# Sheet2.net
KiCad netlist of a schematic drawn in Altium Designer
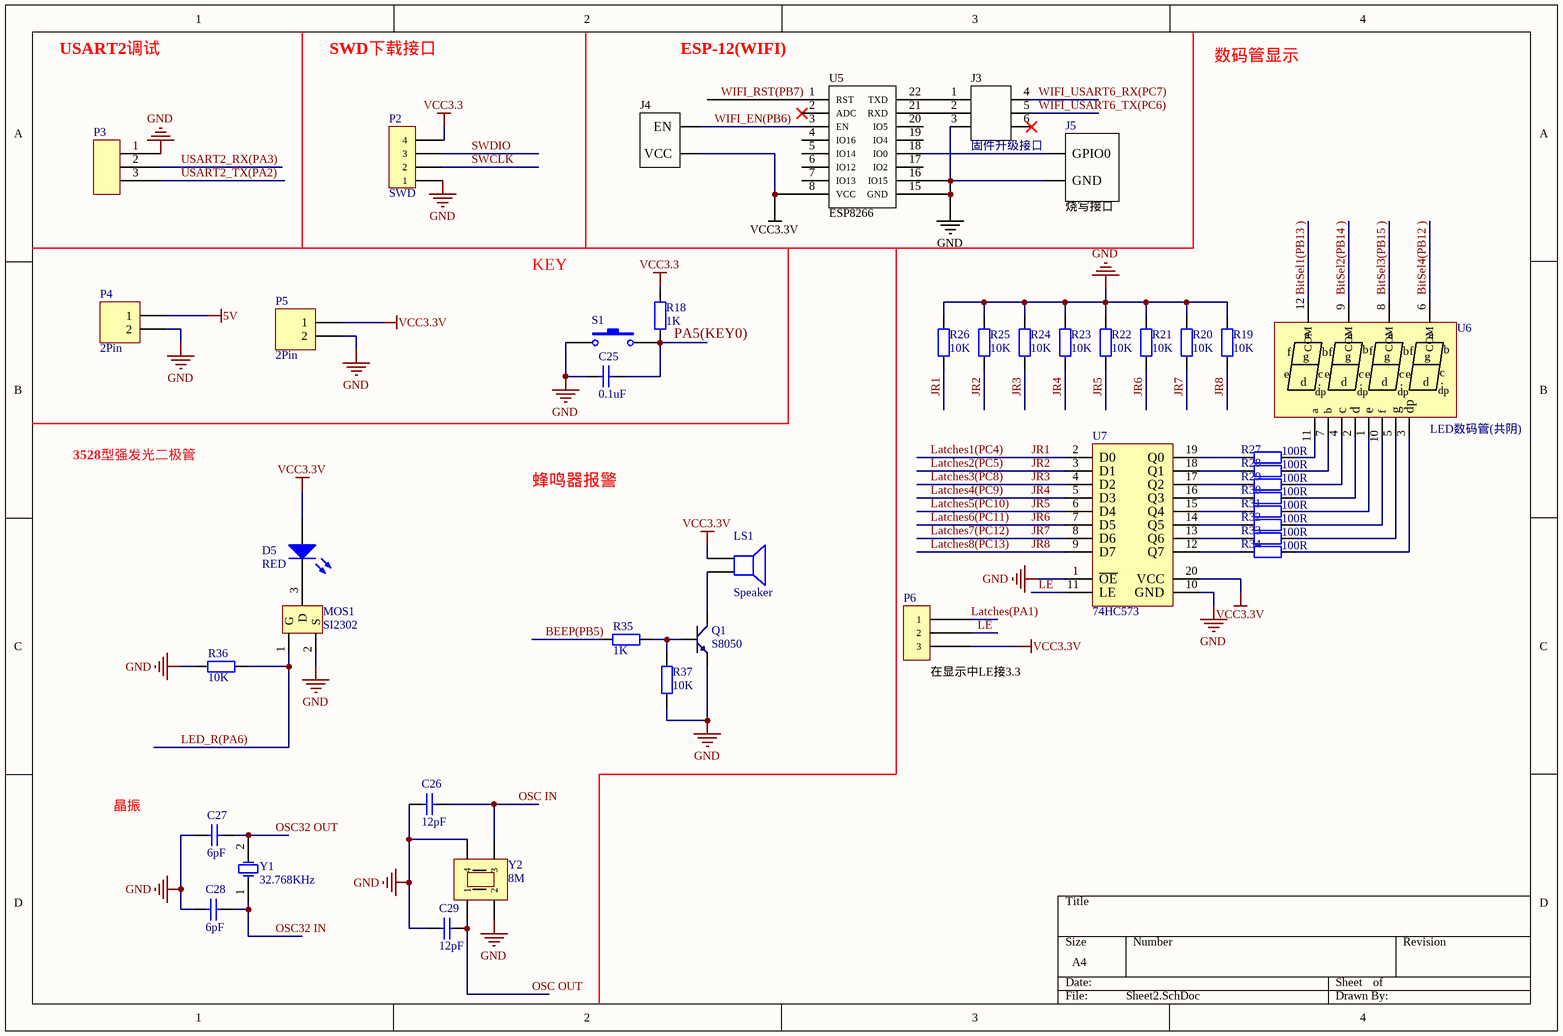
[diagram p0: Sheet2.SchDoc]

(export (version "E")
  (design (tool "Eeschema 10.0.6"))
  (components
    (comp (ref "C25")
      (value "0.1uF")
      (footprint "LC-0603_C(普通电容)")
      (description "贴片电容")
      (fields (field (name "PUBLISHER") "Altium Limited"))
      (libsource (lib "Miscellaneous Devices") (part "Cap Semi"))
    )
    (comp (ref "C26")
      (value "22pF")
      (footprint "LC-0603_C(普通电容)")
      (description "贴片电阻")
      (fields (field (name "值") "12pF") (field (name "PUBLISHER") "Altium Limited"))
      (libsource (lib "Miscellaneous Devices") (part "Cap Semi"))
    )
    (comp (ref "C27")
      (value "6pF")
      (footprint "LC-0603_C(普通电容)")
      (description "贴片电阻")
      (fields (field (name "PUBLISHER") "Altium Limited"))
      (libsource (lib "Miscellaneous Devices") (part "Cap Semi"))
    )
    (comp (ref "C28")
      (value "6pF")
      (footprint "LC-0603_C(普通电容)")
      (description "贴片电阻")
      (fields (field (name "值") "6pF") (field (name "PUBLISHER") "Altium Limited"))
      (libsource (lib "Miscellaneous Devices") (part "Cap Semi"))
    )
    (comp (ref "C29")
      (value "22pF")
      (footprint "LC-0603_C(普通电容)")
      (description "贴片电容")
      (fields (field (name "值") "12pF") (field (name "PUBLISHER") "Altium Limited"))
      (libsource (lib "Miscellaneous Devices") (part "Cap Semi"))
    )
    (comp (ref "D5")
      (value "RED")
      (footprint "发光二极管(CASE-B_3528国星光电)")
      (description "发光二极管")
      (libsource (lib "Miscellaneous Devices") (part "LED2"))
    )
    (comp (ref "J3")
      (value "固件升级接口")
      (footprint "Header2*3 2.54mm")
      (description "固件升级接口2.54mm")
      (libsource (lib "Schlib1") (part "Header2*3"))
    )
    (comp (ref "J4")
      (value "烧录接口")
      (footprint "Header1*2 2.54mm")
      (description "烧录接口2.54mm")
      (libsource (lib "Schlib1") (part "ESP烧录"))
    )
    (comp (ref "J5")
      (value "烧写接口")
      (footprint "Header1*2 2.54mm")
      (description "烧写接口2.54mm")
      (libsource (lib "Schlib1") (part "Header1*2 2.54mm"))
    )
    (comp (ref "LS1")
      (value "Speaker")
      (footprint "PcbLib1:BEEP")
      (description "Loudspeaker")
      (libsource (lib "Schlib1") (part "Speaker"))
    )
    (comp (ref "MOS1")
      (value "SI2302")
      (footprint "MOS(SOP-23美微科)")
      (description "AP2306")
      (libsource (lib "Schlib1") (part "MOS-N"))
    )
    (comp (ref "P2")
      (value "SWD")
      (footprint "Header1*4 2.54MM")
      (description "杜邦线2.54")
      (libsource (lib "PCB") (part "JMP2"))
    )
    (comp (ref "P3")
      (value "串口2调试")
      (footprint "Header1*3 2.54mm")
      (description "排针 2.54MM")
      (libsource (lib "PCB") (part "SIP"))
    )
    (comp (ref "P4")
      (value "2Pin")
      (footprint "PcbLib1:Header1*2 2.54mm")
      (description "Header, 2-Pin")
      (libsource (lib "Schlib1") (part "Header 2"))
    )
    (comp (ref "P5")
      (value "2Pin")
      (footprint "PcbLib1:Header1*2 2.54mm")
      (description "Header, 2-Pin")
      (libsource (lib "Schlib1") (part "Header 2"))
    )
    (comp (ref "P6")
      (value "3P供电选择")
      (footprint "Header1*3 2.54mm")
      (description "排针 2.54MM")
      (libsource (lib "Schlib1") (part "SIP"))
    )
    (comp (ref "Q1")
      (value "S8050")
      (footprint "SOP-23(NPN江苏长电)")
      (description "NPN")
      (libsource (lib "Schlib1") (part "S8050"))
    )
    (comp (ref "R18")
      (value "1K")
      (footprint "LC-0603_R(电阻)")
      (description "贴片电阻")
      (fields (field (name "PUBLISHER") "Altium Limited"))
      (libsource (lib "") (part "Res2_2"))
    )
    (comp (ref "R19")
      (value "10K")
      (footprint "LC-0603_R(电阻)")
      (description "贴片电阻")
      (fields (field (name "Comment") "10k") (field (name "PUBLISHER") "Altium Limited"))
      (libsource (lib "Miscellaneous Devices") (part "Res2"))
    )
    (comp (ref "R20")
      (value "10K")
      (footprint "LC-0603_R(电阻)")
      (description "贴片电阻")
      (fields (field (name "Comment") "10k") (field (name "PUBLISHER") "Altium Limited"))
      (libsource (lib "Miscellaneous Devices") (part "Res2"))
    )
    (comp (ref "R21")
      (value "10K")
      (footprint "LC-0603_R(电阻)")
      (description "贴片电阻")
      (fields (field (name "Comment") "10k") (field (name "PUBLISHER") "Altium Limited"))
      (libsource (lib "Miscellaneous Devices") (part "Res2"))
    )
    (comp (ref "R22")
      (value "10K")
      (footprint "LC-0603_R(电阻)")
      (description "贴片电阻")
      (fields (field (name "Comment") "10k") (field (name "PUBLISHER") "Altium Limited"))
      (libsource (lib "Miscellaneous Devices") (part "Res2"))
    )
    (comp (ref "R23")
      (value "10K")
      (footprint "LC-0603_R(电阻)")
      (description "贴片电阻")
      (fields (field (name "Comment") "10k") (field (name "PUBLISHER") "Altium Limited"))
      (libsource (lib "Miscellaneous Devices") (part "Res2"))
    )
    (comp (ref "R24")
      (value "10K")
      (footprint "LC-0603_R(电阻)")
      (description "贴片电阻")
      (fields (field (name "Comment") "10k") (field (name "PUBLISHER") "Altium Limited"))
      (libsource (lib "Miscellaneous Devices") (part "Res2"))
    )
    (comp (ref "R25")
      (value "10K")
      (footprint "LC-0603_R(电阻)")
      (description "贴片电阻")
      (fields (field (name "Comment") "10k") (field (name "PUBLISHER") "Altium Limited"))
      (libsource (lib "Miscellaneous Devices") (part "Res2"))
    )
    (comp (ref "R26")
      (value "10K")
      (footprint "LC-0603_R(电阻)")
      (description "贴片电阻")
      (fields (field (name "Comment") "10k") (field (name "PUBLISHER") "Altium Limited"))
      (libsource (lib "Miscellaneous Devices") (part "Res2"))
    )
    (comp (ref "R27")
      (value "100R")
      (footprint "LC-0603_R(电阻)")
      (description "贴片电阻")
      (fields (field (name "Comment") "10k") (field (name "PUBLISHER") "Altium Limited"))
      (libsource (lib "") (part "Res2_1"))
    )
    (comp (ref "R28")
      (value "100R")
      (footprint "LC-0603_R(电阻)")
      (description "贴片电阻")
      (fields (field (name "Comment") "10k") (field (name "PUBLISHER") "Altium Limited"))
      (libsource (lib "") (part "Res2_1"))
    )
    (comp (ref "R29")
      (value "100R")
      (footprint "LC-0603_R(电阻)")
      (description "贴片电阻")
      (fields (field (name "Comment") "10k") (field (name "PUBLISHER") "Altium Limited"))
      (libsource (lib "") (part "Res2_1"))
    )
    (comp (ref "R30")
      (value "100R")
      (footprint "LC-0603_R(电阻)")
      (description "贴片电阻")
      (fields (field (name "Comment") "10k") (field (name "PUBLISHER") "Altium Limited"))
      (libsource (lib "") (part "Res2_1"))
    )
    (comp (ref "R31")
      (value "100R")
      (footprint "LC-0603_R(电阻)")
      (description "贴片电阻")
      (fields (field (name "Comment") "10k") (field (name "PUBLISHER") "Altium Limited"))
      (libsource (lib "") (part "Res2_1"))
    )
    (comp (ref "R32")
      (value "100R")
      (footprint "LC-0603_R(电阻)")
      (description "贴片电阻")
      (fields (field (name "Comment") "10k") (field (name "PUBLISHER") "Altium Limited"))
      (libsource (lib "") (part "Res2_1"))
    )
    (comp (ref "R33")
      (value "100R")
      (footprint "LC-0603_R(电阻)")
      (description "贴片电阻")
      (fields (field (name "Comment") "10k") (field (name "PUBLISHER") "Altium Limited"))
      (libsource (lib "") (part "Res2_1"))
    )
    (comp (ref "R34")
      (value "100R")
      (footprint "LC-0603_R(电阻)")
      (description "贴片电阻")
      (fields (field (name "Comment") "10k") (field (name "PUBLISHER") "Altium Limited"))
      (libsource (lib "") (part "Res2_1"))
    )
    (comp (ref "R35")
      (value "1K")
      (footprint "LC-0603_R(电阻)")
      (description "贴片电阻")
      (fields (field (name "Comment") "10k") (field (name "PUBLISHER") "Altium Limited"))
      (libsource (lib "") (part "Res2_1"))
    )
    (comp (ref "R36")
      (value "10K")
      (footprint "LC-0603_R(电阻)")
      (description "贴片电阻")
      (fields (field (name "Comment") "10k") (field (name "PUBLISHER") "Altium Limited"))
      (libsource (lib "") (part "Res2_1"))
    )
    (comp (ref "R37")
      (value "10K")
      (footprint "LC-0603_R(电阻)")
      (description "贴片电阻")
      (fields (field (name "Comment") "10k") (field (name "PUBLISHER") "Altium Limited"))
      (libsource (lib "Miscellaneous Devices") (part "Res2"))
    )
    (comp (ref "S1")
      (value "SW-PB")
      (footprint "key-4p")
      (description "轻触开关 3*6*2.5mm 白头")
      (fields (field (name "PUBLISHER") "Altium Limited"))
      (libsource (lib "Miscellaneous Devices") (part "SW-PB"))
    )
    (comp (ref "U5")
      (value "ESP8266")
      (footprint "ESP8266")
      (description "ESP-12F")
      (libsource (lib "Schlib1") (part "ESP8266"))
    )
    (comp (ref "U6")
      (value "LED数码管(共阴)")
      (footprint "4位共阴数码管(0.36mm 30*14)")
      (description "共阴数码管")
      (libsource (lib "Schlib1") (part "4位8段数码管"))
    )
    (comp (ref "U7")
      (value "74HC573")
      (footprint "SOIC-20_300mil(74HC573)")
      (description "锁存器")
      (libsource (lib "Schlib1") (part "74HC573"))
    )
    (comp (ref "Y1")
      (value "32.768KHz")
      (footprint "NX3215晶振")
      (description "FC135 32.768K 12.5PF 20ppm")
      (libsource (lib "MiniSTM32 V2.0封装库") (part "XTAL"))
    )
    (comp (ref "Y2")
      (value "8M")
      (footprint "SMD3225(8M晶振)")
      (description "25M 20PF 10PPM")
      (libsource (lib "PCB") (part "XTAL"))
    )
  )
  (nets
    (net (code "1") (name "/BEEP(PB5)") (class "Default")
      (node (ref "R35") (pin "2") (pinfunction "2_2") (pintype "passive"))
    )
    (net (code "2") (name "/BitSel1(PB13 )") (class "Default")
      (node (ref "U6") (pin "12") (pinfunction "COM_12") (pintype "passive"))
    )
    (net (code "3") (name "/BitSel2(PB14 )") (class "Default")
      (node (ref "U6") (pin "9") (pinfunction "COM_9") (pintype "passive"))
    )
    (net (code "4") (name "/BitSel3(PB15 )") (class "Default")
      (node (ref "U6") (pin "8") (pinfunction "COM_8") (pintype "passive"))
    )
    (net (code "5") (name "/BitSel4(PB12 )") (class "Default")
      (node (ref "U6") (pin "6") (pinfunction "COM_6") (pintype "passive"))
    )
    (net (code "6") (name "/JR1") (class "Default")
      (node (ref "R26") (pin "2") (pinfunction "2_2") (pintype "passive"))
      (node (ref "U7") (pin "2") (pinfunction "D0_2") (pintype "passive"))
    )
    (net (code "7") (name "/JR2") (class "Default")
      (node (ref "R25") (pin "2") (pinfunction "2_2") (pintype "passive"))
      (node (ref "U7") (pin "3") (pinfunction "D1_3") (pintype "passive"))
    )
    (net (code "8") (name "/JR3") (class "Default")
      (node (ref "R24") (pin "2") (pinfunction "2_2") (pintype "passive"))
      (node (ref "U7") (pin "4") (pinfunction "D2_4") (pintype "passive"))
    )
    (net (code "9") (name "/JR4") (class "Default")
      (node (ref "R23") (pin "2") (pinfunction "2_2") (pintype "passive"))
      (node (ref "U7") (pin "5") (pinfunction "D3_5") (pintype "passive"))
    )
    (net (code "10") (name "/JR5") (class "Default")
      (node (ref "R22") (pin "2") (pinfunction "2_2") (pintype "passive"))
      (node (ref "U7") (pin "6") (pinfunction "D4_6") (pintype "passive"))
    )
    (net (code "11") (name "/JR6") (class "Default")
      (node (ref "R21") (pin "2") (pinfunction "2_2") (pintype "passive"))
      (node (ref "U7") (pin "7") (pinfunction "D5_7") (pintype "passive"))
    )
    (net (code "12") (name "/JR7") (class "Default")
      (node (ref "R20") (pin "2") (pinfunction "2_2") (pintype "passive"))
      (node (ref "U7") (pin "8") (pinfunction "D6_8") (pintype "passive"))
    )
    (net (code "13") (name "/JR8") (class "Default")
      (node (ref "R19") (pin "2") (pinfunction "2_2") (pintype "passive"))
      (node (ref "U7") (pin "9") (pinfunction "D7_9") (pintype "passive"))
    )
    (net (code "14") (name "/LE") (class "Default")
      (node (ref "P6") (pin "2") (pinfunction "2_2") (pintype "passive"))
      (node (ref "U7") (pin "11") (pinfunction "LE_11") (pintype "passive"))
    )
    (net (code "15") (name "/LED_R(PA6)") (class "Default")
      (node (ref "MOS1") (pin "1") (pinfunction "G_1") (pintype "passive"))
      (node (ref "R36") (pin "1") (pinfunction "1_1") (pintype "passive"))
    )
    (net (code "16") (name "/Latches(PA1)") (class "Default")
      (node (ref "P6") (pin "1") (pinfunction "1_1") (pintype "passive"))
    )
    (net (code "17") (name "/OSC IN") (class "Default")
      (node (ref "C26") (pin "1") (pinfunction "1_1") (pintype "passive"))
      (node (ref "Y2") (pin "3") (pinfunction "3_3") (pintype "passive"))
    )
    (net (code "18") (name "/OSC OUT") (class "Default")
      (node (ref "C29") (pin "1") (pinfunction "1_1") (pintype "passive"))
      (node (ref "Y2") (pin "1") (pinfunction "1_1") (pintype "passive"))
    )
    (net (code "19") (name "/OSC32 IN") (class "Default")
      (node (ref "C28") (pin "1") (pinfunction "1_1") (pintype "passive"))
      (node (ref "Y1") (pin "1") (pinfunction "OSC1_1") (pintype "passive"))
    )
    (net (code "20") (name "/OSC32 OUT") (class "Default")
      (node (ref "C27") (pin "1") (pinfunction "1_1") (pintype "passive"))
      (node (ref "Y1") (pin "2") (pinfunction "OSC2_2") (pintype "passive"))
    )
    (net (code "21") (name "/PA5(KEY0)") (class "Default")
      (node (ref "C25") (pin "1") (pinfunction "1_1") (pintype "passive"))
      (node (ref "R18") (pin "1") (pinfunction "1_1") (pintype "passive"))
      (node (ref "S1") (pin "2") (pinfunction "2_2") (pintype "passive"))
    )
    (net (code "22") (name "/SWCLK") (class "Default")
      (node (ref "P2") (pin "2") (pinfunction "2_2") (pintype "passive"))
    )
    (net (code "23") (name "/SWDIO") (class "Default")
      (node (ref "P2") (pin "3") (pinfunction "3_3") (pintype "passive"))
    )
    (net (code "24") (name "/USART2_RX(PA3)") (class "Default")
      (node (ref "P3") (pin "2") (pinfunction "PA10(USART1_RX)_2") (pintype "passive"))
    )
    (net (code "25") (name "/USART2_TX(PA2)") (class "Default")
      (node (ref "P3") (pin "3") (pinfunction "PA9(USART1_TX)_3") (pintype "passive"))
    )
    (net (code "26") (name "/WIFI_EN(PB6)") (class "Default")
      (node (ref "J4") (pin "2") (pinfunction "EN_2") (pintype "passive"))
      (node (ref "U5") (pin "3") (pinfunction "EN_3") (pintype "passive"))
    )
    (net (code "27") (name "/WIFI_RST(PB7)") (class "Default")
      (node (ref "U5") (pin "1") (pinfunction "RST_1") (pintype "passive"))
    )
    (net (code "28") (name "/WIFI_USART6_RX(PC7)") (class "Default")
      (node (ref "J3") (pin "4") (pinfunction "RXD_4") (pintype "passive"))
    )
    (net (code "29") (name "/WIFI_USART6_TX(PC6)") (class "Default")
      (node (ref "J3") (pin "5") (pinfunction "TXD_5") (pintype "passive"))
    )
    (net (code "30") (name "5V") (class "Default")
      (node (ref "P4") (pin "1") (pinfunction "1_1") (pintype "passive"))
    )
    (net (code "31") (name "GND") (class "Default")
      (node (ref "C25") (pin "2") (pinfunction "2_2") (pintype "passive"))
      (node (ref "C26") (pin "2") (pinfunction "2_2") (pintype "passive"))
      (node (ref "C27") (pin "2") (pinfunction "2_2") (pintype "passive"))
      (node (ref "C28") (pin "2") (pinfunction "2_2") (pintype "passive"))
      (node (ref "C29") (pin "2") (pinfunction "2_2") (pintype "passive"))
      (node (ref "J3") (pin "3") (pinfunction "GND_3") (pintype "passive"))
      (node (ref "J5") (pin "2") (pinfunction "GND_2") (pintype "passive"))
      (node (ref "MOS1") (pin "2") (pinfunction "S_2") (pintype "passive"))
      (node (ref "P2") (pin "1") (pinfunction "1_1") (pintype "passive"))
      (node (ref "P3") (pin "1") (pinfunction "GND_1") (pintype "passive"))
      (node (ref "P4") (pin "2") (pinfunction "2_2") (pintype "passive"))
      (node (ref "P5") (pin "2") (pinfunction "2_2") (pintype "passive"))
      (node (ref "Q1") (pin "2") (pinfunction "E_2") (pintype "passive"))
      (node (ref "R19") (pin "1") (pinfunction "1_1") (pintype "passive"))
      (node (ref "R20") (pin "1") (pinfunction "1_1") (pintype "passive"))
      (node (ref "R21") (pin "1") (pinfunction "1_1") (pintype "passive"))
      (node (ref "R22") (pin "1") (pinfunction "1_1") (pintype "passive"))
      (node (ref "R23") (pin "1") (pinfunction "1_1") (pintype "passive"))
      (node (ref "R24") (pin "1") (pinfunction "1_1") (pintype "passive"))
      (node (ref "R25") (pin "1") (pinfunction "1_1") (pintype "passive"))
      (node (ref "R26") (pin "1") (pinfunction "1_1") (pintype "passive"))
      (node (ref "R36") (pin "2") (pinfunction "2_2") (pintype "passive"))
      (node (ref "R37") (pin "2") (pinfunction "2_2") (pintype "passive"))
      (node (ref "S1") (pin "1") (pinfunction "1_1") (pintype "passive"))
      (node (ref "U5") (pin "15") (pinfunction "GND_15") (pintype "passive"))
      (node (ref "U5") (pin "16") (pinfunction "IO15_16") (pintype "passive"))
      (node (ref "U7") (pin "1") (pinfunction "~{OE}_1") (pintype "passive"))
      (node (ref "U7") (pin "10") (pinfunction "GND_10") (pintype "passive"))
      (node (ref "Y2") (pin "2") (pinfunction "2_2") (pintype "passive"))
      (node (ref "Y2") (pin "4") (pinfunction "4_4") (pintype "passive"))
    )
    (net (code "32") (name "Net-(D5-K)") (class "Default")
      (node (ref "D5") (pin "2") (pinfunction "K_2") (pintype "passive"))
      (node (ref "MOS1") (pin "3") (pinfunction "D_3") (pintype "passive"))
    )
    (net (code "33") (name "Net-(J5-GPIO0)") (class "Default")
      (node (ref "J5") (pin "1") (pinfunction "GPIO0_1") (pintype "passive"))
      (node (ref "U5") (pin "18") (pinfunction "IO0_18") (pintype "passive"))
    )
    (net (code "34") (name "Net-(Q1-B)") (class "Default")
      (node (ref "Q1") (pin "1") (pinfunction "B_1") (pintype "passive"))
      (node (ref "R35") (pin "1") (pinfunction "1_1") (pintype "passive"))
      (node (ref "R37") (pin "1") (pinfunction "1_1") (pintype "passive"))
    )
    (net (code "35") (name "Net-(Q1-C)") (class "Default")
      (node (ref "LS1") (pin "2") (pinfunction "2_2") (pintype "passive"))
      (node (ref "Q1") (pin "3") (pinfunction "C_3") (pintype "passive"))
    )
    (net (code "36") (name "Net-(U5-RXD)") (class "Default")
      (node (ref "J3") (pin "2") (pinfunction "RXD_2") (pintype "passive"))
      (node (ref "U5") (pin "21") (pinfunction "RXD_21") (pintype "passive"))
    )
    (net (code "37") (name "Net-(U5-TXD)") (class "Default")
      (node (ref "J3") (pin "1") (pinfunction "TXD_1") (pintype "passive"))
      (node (ref "U5") (pin "22") (pinfunction "TXD_22") (pintype "passive"))
    )
    (net (code "38") (name "Net-(U6-a)") (class "Default")
      (node (ref "R27") (pin "1") (pinfunction "1_1") (pintype "passive"))
      (node (ref "U6") (pin "11") (pinfunction "a_11") (pintype "passive"))
    )
    (net (code "39") (name "Net-(U6-b)") (class "Default")
      (node (ref "R28") (pin "1") (pinfunction "1_1") (pintype "passive"))
      (node (ref "U6") (pin "7") (pinfunction "b_7") (pintype "passive"))
    )
    (net (code "40") (name "Net-(U6-c)") (class "Default")
      (node (ref "R29") (pin "1") (pinfunction "1_1") (pintype "passive"))
      (node (ref "U6") (pin "4") (pinfunction "c_4") (pintype "passive"))
    )
    (net (code "41") (name "Net-(U6-d)") (class "Default")
      (node (ref "R30") (pin "1") (pinfunction "1_1") (pintype "passive"))
      (node (ref "U6") (pin "2") (pinfunction "d_2") (pintype "passive"))
    )
    (net (code "42") (name "Net-(U6-dp)") (class "Default")
      (node (ref "R34") (pin "1") (pinfunction "1_1") (pintype "passive"))
      (node (ref "U6") (pin "3") (pinfunction "dp_3") (pintype "passive"))
    )
    (net (code "43") (name "Net-(U6-e)") (class "Default")
      (node (ref "R31") (pin "1") (pinfunction "1_1") (pintype "passive"))
      (node (ref "U6") (pin "1") (pinfunction "e_1") (pintype "passive"))
    )
    (net (code "44") (name "Net-(U6-f)") (class "Default")
      (node (ref "R32") (pin "1") (pinfunction "1_1") (pintype "passive"))
      (node (ref "U6") (pin "10") (pinfunction "f_10") (pintype "passive"))
    )
    (net (code "45") (name "Net-(U6-g)") (class "Default")
      (node (ref "R33") (pin "1") (pinfunction "1_1") (pintype "passive"))
      (node (ref "U6") (pin "5") (pinfunction "g_5") (pintype "passive"))
    )
    (net (code "46") (name "Net-(U7-Q0)") (class "Default")
      (node (ref "R27") (pin "2") (pinfunction "2_2") (pintype "passive"))
      (node (ref "U7") (pin "19") (pinfunction "Q0_19") (pintype "passive"))
    )
    (net (code "47") (name "Net-(U7-Q1)") (class "Default")
      (node (ref "R28") (pin "2") (pinfunction "2_2") (pintype "passive"))
      (node (ref "U7") (pin "18") (pinfunction "Q1_18") (pintype "passive"))
    )
    (net (code "48") (name "Net-(U7-Q2)") (class "Default")
      (node (ref "R29") (pin "2") (pinfunction "2_2") (pintype "passive"))
      (node (ref "U7") (pin "17") (pinfunction "Q2_17") (pintype "passive"))
    )
    (net (code "49") (name "Net-(U7-Q3)") (class "Default")
      (node (ref "R30") (pin "2") (pinfunction "2_2") (pintype "passive"))
      (node (ref "U7") (pin "16") (pinfunction "Q3_16") (pintype "passive"))
    )
    (net (code "50") (name "Net-(U7-Q4)") (class "Default")
      (node (ref "R31") (pin "2") (pinfunction "2_2") (pintype "passive"))
      (node (ref "U7") (pin "15") (pinfunction "Q4_15") (pintype "passive"))
    )
    (net (code "51") (name "Net-(U7-Q5)") (class "Default")
      (node (ref "R32") (pin "2") (pinfunction "2_2") (pintype "passive"))
      (node (ref "U7") (pin "14") (pinfunction "Q5_14") (pintype "passive"))
    )
    (net (code "52") (name "Net-(U7-Q6)") (class "Default")
      (node (ref "R33") (pin "2") (pinfunction "2_2") (pintype "passive"))
      (node (ref "U7") (pin "13") (pinfunction "Q6_13") (pintype "passive"))
    )
    (net (code "53") (name "Net-(U7-Q7)") (class "Default")
      (node (ref "R34") (pin "2") (pinfunction "2_2") (pintype "passive"))
      (node (ref "U7") (pin "12") (pinfunction "Q7_12") (pintype "passive"))
    )
    (net (code "54") (name "VCC3.3") (class "Default")
      (node (ref "P2") (pin "4") (pinfunction "4_4") (pintype "passive"))
      (node (ref "R18") (pin "2") (pinfunction "2_2") (pintype "passive"))
    )
    (net (code "55") (name "VCC3.3V") (class "Default")
      (node (ref "D5") (pin "1") (pinfunction "A_1") (pintype "passive"))
      (node (ref "J4") (pin "1") (pinfunction "VCC_1") (pintype "passive"))
      (node (ref "LS1") (pin "1") (pinfunction "1_1") (pintype "passive"))
      (node (ref "P5") (pin "1") (pinfunction "1_1") (pintype "passive"))
      (node (ref "P6") (pin "3") (pinfunction "3_3") (pintype "passive"))
      (node (ref "U5") (pin "8") (pinfunction "VCC_8") (pintype "passive"))
      (node (ref "U7") (pin "20") (pinfunction "VCC_20") (pintype "passive"))
    )
    (net (code "56") (name "unconnected-(J3-GND-Pad6)") (class "Default")
      (node (ref "J3") (pin "6") (pinfunction "GND_6") (pintype "passive+no_connect"))
    )
    (net (code "57") (name "unconnected-(U5-ADC-Pad2)") (class "Default")
      (node (ref "U5") (pin "2") (pinfunction "ADC_2") (pintype "passive+no_connect"))
    )
    (net (code "58") (name "unconnected-(U5-IO2-Pad17)") (class "Default")
      (node (ref "U5") (pin "17") (pinfunction "IO2_17") (pintype "passive"))
    )
    (net (code "59") (name "unconnected-(U5-IO4-Pad19)") (class "Default")
      (node (ref "U5") (pin "19") (pinfunction "IO4_19") (pintype "passive"))
    )
    (net (code "60") (name "unconnected-(U5-IO5-Pad20)") (class "Default")
      (node (ref "U5") (pin "20") (pinfunction "IO5_20") (pintype "passive"))
    )
    (net (code "61") (name "unconnected-(U5-IO12-Pad6)") (class "Default")
      (node (ref "U5") (pin "6") (pinfunction "IO12_6") (pintype "passive"))
    )
    (net (code "62") (name "unconnected-(U5-IO13-Pad7)") (class "Default")
      (node (ref "U5") (pin "7") (pinfunction "IO13_7") (pintype "passive"))
    )
    (net (code "63") (name "unconnected-(U5-IO14-Pad5)") (class "Default")
      (node (ref "U5") (pin "5") (pinfunction "IO14_5") (pintype "passive"))
    )
    (net (code "64") (name "unconnected-(U5-IO16-Pad4)") (class "Default")
      (node (ref "U5") (pin "4") (pinfunction "IO16_4") (pintype "passive"))
    )
  )
)
